# dual_seq_v1_0_1_main.net
KiCad netlist of a schematic drawn in EAGLE
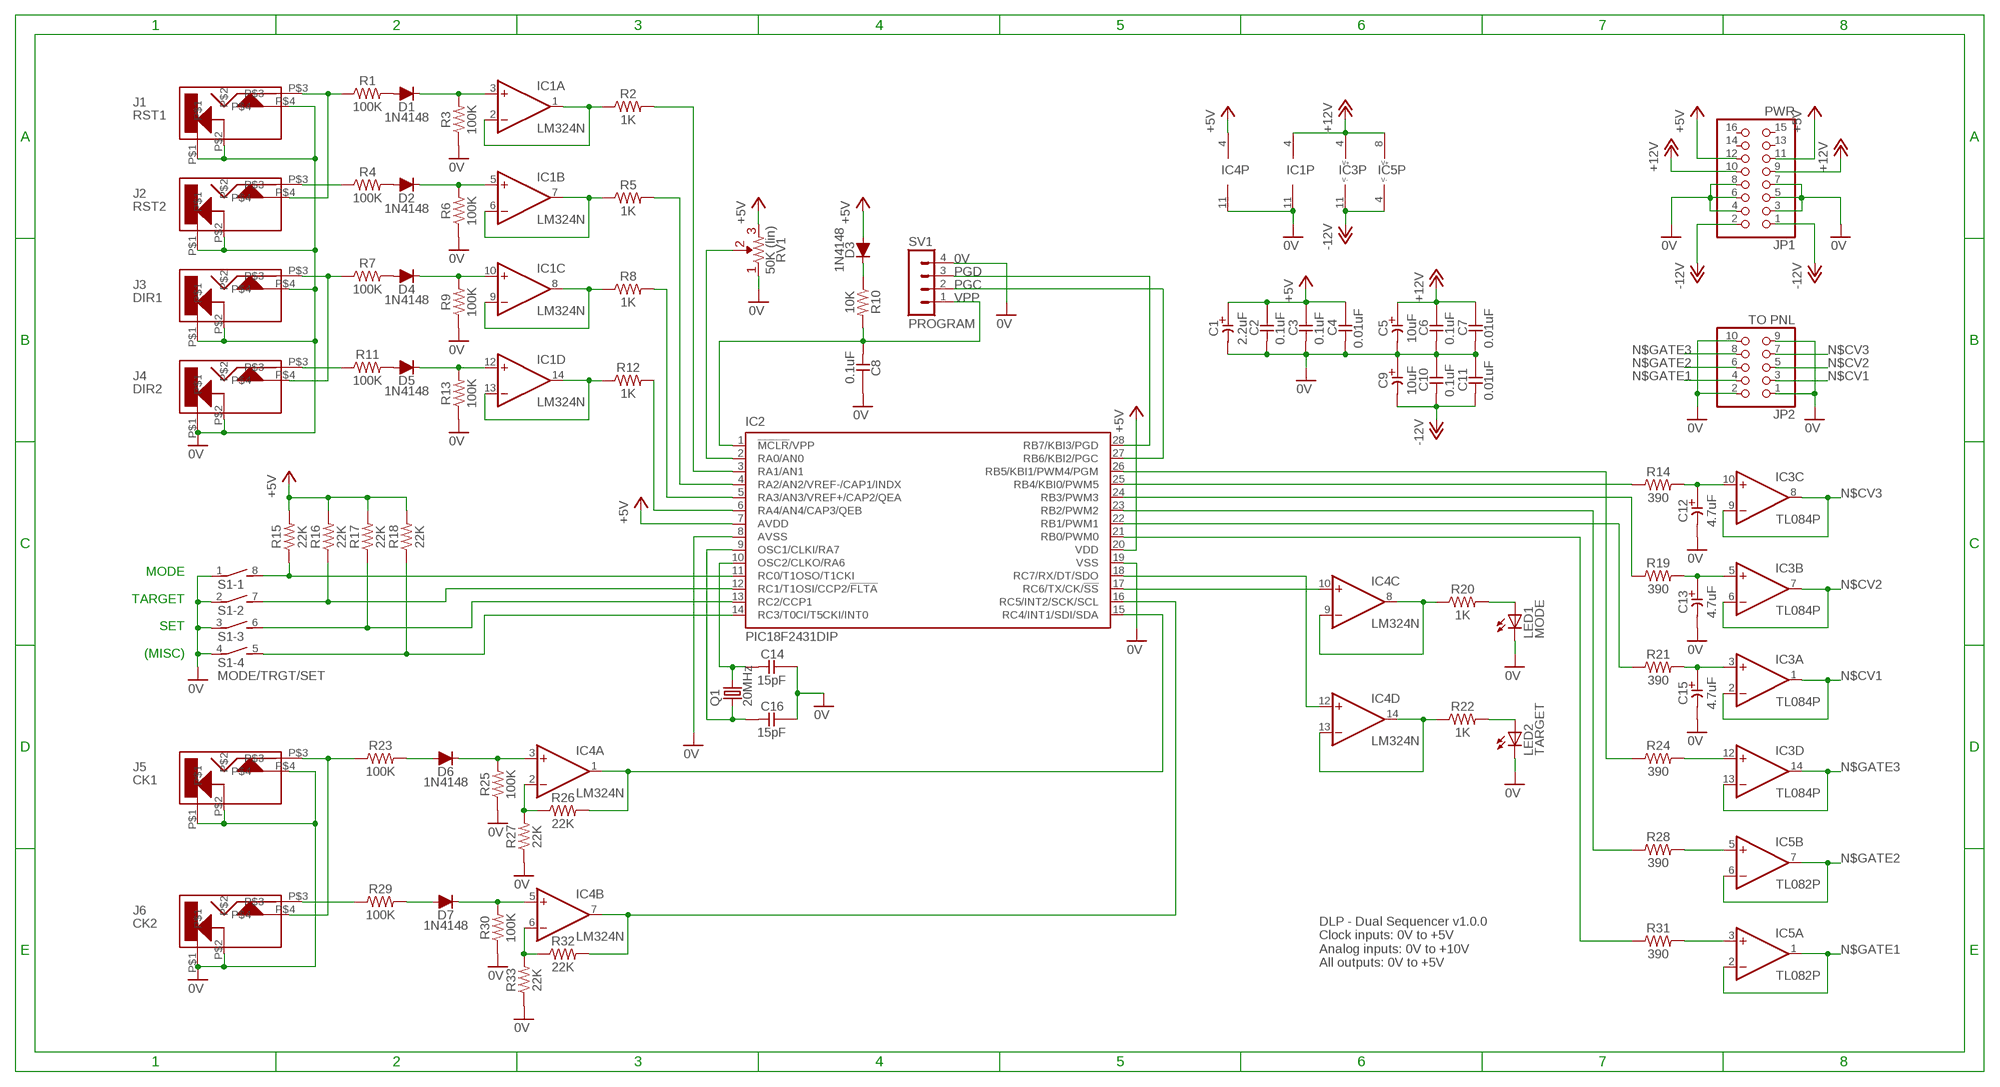
[diagram p0: schematic, sheet 1]

(export (version "E")
  (design (tool "Eeschema 10.0.6"))
  (components
    (comp (ref "C1")
      (value "2.2uF")
      (footprint "eagle-import:E2-5")
      (libsource (lib "eagle-import") (part "CE-USE2-5"))
    )
    (comp (ref "C2")
      (value "0.1uF")
      (footprint "eagle-import:C025-024X044")
      (libsource (lib "eagle-import") (part "CC-US025-024X044"))
    )
    (comp (ref "C3")
      (value "0.1uF")
      (footprint "eagle-import:C025-024X044")
      (libsource (lib "eagle-import") (part "CC-US025-024X044"))
    )
    (comp (ref "C4")
      (value "0.01uF")
      (footprint "eagle-import:C025-024X044")
      (libsource (lib "eagle-import") (part "CC-US025-024X044"))
    )
    (comp (ref "C5")
      (value "10uF")
      (footprint "eagle-import:E2-5")
      (libsource (lib "eagle-import") (part "CE-USE2-5"))
    )
    (comp (ref "C6")
      (value "0.1uF")
      (footprint "eagle-import:C025-024X044")
      (libsource (lib "eagle-import") (part "CC-US025-024X044"))
    )
    (comp (ref "C7")
      (value "0.01uF")
      (footprint "eagle-import:C025-024X044")
      (libsource (lib "eagle-import") (part "CC-US025-024X044"))
    )
    (comp (ref "C8")
      (value "0.1uF")
      (footprint "eagle-import:C025-024X044")
      (libsource (lib "eagle-import") (part "CC-US025-024X044"))
    )
    (comp (ref "C9")
      (value "10uF")
      (footprint "eagle-import:E2-5")
      (libsource (lib "eagle-import") (part "CE-USE2-5"))
    )
    (comp (ref "C10")
      (value "0.1uF")
      (footprint "eagle-import:C025-024X044")
      (libsource (lib "eagle-import") (part "CC-US025-024X044"))
    )
    (comp (ref "C11")
      (value "0.01uF")
      (footprint "eagle-import:C025-024X044")
      (libsource (lib "eagle-import") (part "CC-US025-024X044"))
    )
    (comp (ref "C12")
      (value "4.7uF")
      (footprint "eagle-import:E2-5")
      (libsource (lib "eagle-import") (part "CE-USE2-5"))
    )
    (comp (ref "C13")
      (value "4.7uF")
      (footprint "eagle-import:E2-5")
      (libsource (lib "eagle-import") (part "CE-USE2-5"))
    )
    (comp (ref "C14")
      (value "15pF")
      (footprint "eagle-import:C025-024X044")
      (libsource (lib "eagle-import") (part "CC-US025-024X044"))
    )
    (comp (ref "C15")
      (value "4.7uF")
      (footprint "eagle-import:E2-5")
      (libsource (lib "eagle-import") (part "CE-USE2-5"))
    )
    (comp (ref "C16")
      (value "15pF")
      (footprint "eagle-import:C025-024X044")
      (libsource (lib "eagle-import") (part "CC-US025-024X044"))
    )
    (comp (ref "D1")
      (value "1N4148")
      (footprint "eagle-import:DO34-5")
      (libsource (lib "eagle-import") (part "1N4148"))
    )
    (comp (ref "D2")
      (value "1N4148")
      (footprint "eagle-import:DO34-5")
      (libsource (lib "eagle-import") (part "1N4148"))
    )
    (comp (ref "D3")
      (value "1N4148")
      (footprint "eagle-import:DO34-5")
      (libsource (lib "eagle-import") (part "1N4148"))
    )
    (comp (ref "D4")
      (value "1N4148")
      (footprint "eagle-import:DO34-5")
      (libsource (lib "eagle-import") (part "1N4148"))
    )
    (comp (ref "D5")
      (value "1N4148")
      (footprint "eagle-import:DO34-5")
      (libsource (lib "eagle-import") (part "1N4148"))
    )
    (comp (ref "D6")
      (value "1N4148")
      (footprint "eagle-import:DO34-5")
      (libsource (lib "eagle-import") (part "1N4148"))
    )
    (comp (ref "D7")
      (value "1N4148")
      (footprint "eagle-import:DO34-5")
      (libsource (lib "eagle-import") (part "1N4148"))
    )
    (comp (ref "IC1")
      (value "LM324N")
      (footprint "eagle-import:DIL14")
      (libsource (lib "eagle-import") (part "LM324N"))
    )
    (comp (ref "IC2")
      (value "PIC18F2431DIP")
      (footprint "eagle-import:DIL28-3")
      (fields (field (name "MF") "MICROCHIP") (field (name "MPN") "PIC18F2431-I/SP"))
      (libsource (lib "eagle-import") (part "PIC18F231DIP4"))
    )
    (comp (ref "IC3")
      (value "TL084P")
      (footprint "eagle-import:DIL14")
      (libsource (lib "eagle-import") (part "TL084P"))
    )
    (comp (ref "IC4")
      (value "LM324N")
      (footprint "eagle-import:DIL14")
      (libsource (lib "eagle-import") (part "LM324N"))
    )
    (comp (ref "IC5")
      (value "TL082P")
      (footprint "eagle-import:DIL08")
      (libsource (lib "eagle-import") (part "TL082P"))
    )
    (comp (ref "J1")
      (value "RST1")
      (footprint "eagle-import:CL1384")
      (libsource (lib "eagle-import") (part "CL1384"))
    )
    (comp (ref "J2")
      (value "RST2")
      (footprint "eagle-import:CL1384")
      (libsource (lib "eagle-import") (part "CL1384"))
    )
    (comp (ref "J3")
      (value "DIR1")
      (footprint "eagle-import:CL1384")
      (libsource (lib "eagle-import") (part "CL1384"))
    )
    (comp (ref "J4")
      (value "DIR2")
      (footprint "eagle-import:CL1384")
      (libsource (lib "eagle-import") (part "CL1384"))
    )
    (comp (ref "J5")
      (value "CK1")
      (footprint "eagle-import:CL1384")
      (libsource (lib "eagle-import") (part "CL1384"))
    )
    (comp (ref "J6")
      (value "CK2")
      (footprint "eagle-import:CL1384")
      (libsource (lib "eagle-import") (part "CL1384"))
    )
    (comp (ref "JP1")
      (value "PWR")
      (footprint "eagle-import:2X08")
      (libsource (lib "eagle-import") (part "PINHD-2X8"))
    )
    (comp (ref "JP2")
      (value "TO PNL")
      (footprint "eagle-import:2X05")
      (libsource (lib "eagle-import") (part "PINHD-2X5"))
    )
    (comp (ref "LED1")
      (value "MODE")
      (footprint "eagle-import:LED3MM")
      (libsource (lib "eagle-import") (part "LED3MM"))
    )
    (comp (ref "LED2")
      (value "TARGET")
      (footprint "eagle-import:LED3MM")
      (libsource (lib "eagle-import") (part "LED3MM"))
    )
    (comp (ref "Q1")
      (value "20MHz")
      (footprint "eagle-import:HC49_S")
      (libsource (lib "eagle-import") (part "CRYSTALHC49S"))
    )
    (comp (ref "R1")
      (value "100K")
      (footprint "eagle-import:0207_7")
      (libsource (lib "eagle-import") (part "R"))
    )
    (comp (ref "R2")
      (value "1K")
      (footprint "eagle-import:0207_7")
      (libsource (lib "eagle-import") (part "R"))
    )
    (comp (ref "R3")
      (value "100K")
      (footprint "eagle-import:0207_7")
      (libsource (lib "eagle-import") (part "R"))
    )
    (comp (ref "R4")
      (value "100K")
      (footprint "eagle-import:0207_7")
      (libsource (lib "eagle-import") (part "R"))
    )
    (comp (ref "R5")
      (value "1K")
      (footprint "eagle-import:0207_7")
      (libsource (lib "eagle-import") (part "R"))
    )
    (comp (ref "R6")
      (value "100K")
      (footprint "eagle-import:0207_7")
      (libsource (lib "eagle-import") (part "R"))
    )
    (comp (ref "R7")
      (value "100K")
      (footprint "eagle-import:0207_7")
      (libsource (lib "eagle-import") (part "R"))
    )
    (comp (ref "R8")
      (value "1K")
      (footprint "eagle-import:0207_7")
      (libsource (lib "eagle-import") (part "R"))
    )
    (comp (ref "R9")
      (value "100K")
      (footprint "eagle-import:0207_7")
      (libsource (lib "eagle-import") (part "R"))
    )
    (comp (ref "R10")
      (value "10K")
      (footprint "eagle-import:0207_7")
      (libsource (lib "eagle-import") (part "R"))
    )
    (comp (ref "R11")
      (value "100K")
      (footprint "eagle-import:0207_7")
      (libsource (lib "eagle-import") (part "R"))
    )
    (comp (ref "R12")
      (value "1K")
      (footprint "eagle-import:0207_7")
      (libsource (lib "eagle-import") (part "R"))
    )
    (comp (ref "R13")
      (value "100K")
      (footprint "eagle-import:0207_7")
      (libsource (lib "eagle-import") (part "R"))
    )
    (comp (ref "R14")
      (value "390")
      (footprint "eagle-import:0207_7")
      (libsource (lib "eagle-import") (part "R"))
    )
    (comp (ref "R15")
      (value "22K")
      (footprint "eagle-import:0207_7")
      (libsource (lib "eagle-import") (part "R"))
    )
    (comp (ref "R16")
      (value "22K")
      (footprint "eagle-import:0207_7")
      (libsource (lib "eagle-import") (part "R"))
    )
    (comp (ref "R17")
      (value "22K")
      (footprint "eagle-import:0207_7")
      (libsource (lib "eagle-import") (part "R"))
    )
    (comp (ref "R18")
      (value "22K")
      (footprint "eagle-import:0207_7")
      (libsource (lib "eagle-import") (part "R"))
    )
    (comp (ref "R19")
      (value "390")
      (footprint "eagle-import:0207_7")
      (libsource (lib "eagle-import") (part "R"))
    )
    (comp (ref "R20")
      (value "1K")
      (footprint "eagle-import:0207_7")
      (libsource (lib "eagle-import") (part "R"))
    )
    (comp (ref "R21")
      (value "390")
      (footprint "eagle-import:0207_7")
      (libsource (lib "eagle-import") (part "R"))
    )
    (comp (ref "R22")
      (value "1K")
      (footprint "eagle-import:0207_7")
      (libsource (lib "eagle-import") (part "R"))
    )
    (comp (ref "R23")
      (value "100K")
      (footprint "eagle-import:0207_7")
      (libsource (lib "eagle-import") (part "R"))
    )
    (comp (ref "R24")
      (value "390")
      (footprint "eagle-import:0207_7")
      (libsource (lib "eagle-import") (part "R"))
    )
    (comp (ref "R25")
      (value "100K")
      (footprint "eagle-import:0207_7")
      (libsource (lib "eagle-import") (part "R"))
    )
    (comp (ref "R26")
      (value "22K")
      (footprint "eagle-import:0207_7")
      (libsource (lib "eagle-import") (part "R"))
    )
    (comp (ref "R27")
      (value "22K")
      (footprint "eagle-import:0207_7")
      (libsource (lib "eagle-import") (part "R"))
    )
    (comp (ref "R28")
      (value "390")
      (footprint "eagle-import:0207_7")
      (libsource (lib "eagle-import") (part "R"))
    )
    (comp (ref "R29")
      (value "100K")
      (footprint "eagle-import:0207_7")
      (libsource (lib "eagle-import") (part "R"))
    )
    (comp (ref "R30")
      (value "100K")
      (footprint "eagle-import:0207_7")
      (libsource (lib "eagle-import") (part "R"))
    )
    (comp (ref "R31")
      (value "390")
      (footprint "eagle-import:0207_7")
      (libsource (lib "eagle-import") (part "R"))
    )
    (comp (ref "R32")
      (value "22K")
      (footprint "eagle-import:0207_7")
      (libsource (lib "eagle-import") (part "R"))
    )
    (comp (ref "R33")
      (value "22K")
      (footprint "eagle-import:0207_7")
      (libsource (lib "eagle-import") (part "R"))
    )
    (comp (ref "RV1")
      (value "50K (lin)")
      (footprint "eagle-import:R-VAR")
      (libsource (lib "eagle-import") (part "R-VAR"))
    )
    (comp (ref "S1")
      (value "MODE/TRGT/SET")
      (footprint "eagle-import:DIP04S")
      (libsource (lib "eagle-import") (part "DIP04S"))
    )
    (comp (ref "SV1")
      (value "PROGRAM")
      (footprint "eagle-import:MA04-1")
      (libsource (lib "eagle-import") (part "MA04-1"))
    )
  )
  (nets
    (net (code "1") (name "+5V") (class "Default")
      (node (ref "C1") (pin "+") (pinfunction "+_+") (pintype "passive"))
      (node (ref "C2") (pin "1") (pinfunction "1_1") (pintype "passive"))
      (node (ref "C3") (pin "1") (pinfunction "1_1") (pintype "passive"))
      (node (ref "C4") (pin "1") (pinfunction "1_1") (pintype "passive"))
      (node (ref "D3") (pin "A") (pinfunction "A_A") (pintype "passive"))
      (node (ref "IC2") (pin "20") (pinfunction "VDD_20") (pintype "power_in"))
      (node (ref "IC2") (pin "7") (pinfunction "AVDD_7") (pintype "power_in"))
      (node (ref "IC4") (pin "4") (pinfunction "V+_4") (pintype "power_in"))
      (node (ref "JP1") (pin "11") (pinfunction "11_11") (pintype "passive"))
      (node (ref "JP1") (pin "12") (pinfunction "12_12") (pintype "passive"))
      (node (ref "R15") (pin "2") (pinfunction "2_2") (pintype "passive"))
      (node (ref "R16") (pin "2") (pinfunction "2_2") (pintype "passive"))
      (node (ref "R17") (pin "2") (pinfunction "2_2") (pintype "passive"))
      (node (ref "R18") (pin "2") (pinfunction "2_2") (pintype "passive"))
      (node (ref "RV1") (pin "R2") (pinfunction "2_R2") (pintype "passive"))
    )
    (net (code "2") (name "+12V") (class "Default")
      (node (ref "C5") (pin "+") (pinfunction "+_+") (pintype "passive"))
      (node (ref "C6") (pin "1") (pinfunction "1_1") (pintype "passive"))
      (node (ref "C7") (pin "1") (pinfunction "1_1") (pintype "passive"))
      (node (ref "IC1") (pin "4") (pinfunction "V+_4") (pintype "power_in"))
      (node (ref "IC3") (pin "4") (pinfunction "V+_4") (pintype "power_in"))
      (node (ref "IC5") (pin "8") (pinfunction "V+_8") (pintype "power_in"))
      (node (ref "JP1") (pin "10") (pinfunction "10_10") (pintype "passive"))
      (node (ref "JP1") (pin "9") (pinfunction "9_9") (pintype "passive"))
    )
    (net (code "3") (name "-12V") (class "Default")
      (node (ref "C10") (pin "2") (pinfunction "2_2") (pintype "passive"))
      (node (ref "C11") (pin "2") (pinfunction "2_2") (pintype "passive"))
      (node (ref "C9") (pin "-") (pinfunction "-_-") (pintype "passive"))
      (node (ref "IC3") (pin "11") (pinfunction "V-_11") (pintype "power_in"))
      (node (ref "IC5") (pin "4") (pinfunction "V-_4") (pintype "power_in"))
      (node (ref "JP1") (pin "1") (pinfunction "1_1") (pintype "passive"))
      (node (ref "JP1") (pin "2") (pinfunction "2_2") (pintype "passive"))
    )
    (net (code "4") (name "/N$CV1") (class "Default")
      (node (ref "IC3") (pin "1") (pinfunction "OUT_1") (pintype "output"))
      (node (ref "IC3") (pin "2") (pinfunction "-IN_2") (pintype "input"))
      (node (ref "JP2") (pin "3") (pinfunction "3_3") (pintype "passive"))
    )
    (net (code "5") (name "/N$CV2") (class "Default")
      (node (ref "IC3") (pin "6") (pinfunction "-IN_6") (pintype "input"))
      (node (ref "IC3") (pin "7") (pinfunction "OUT_7") (pintype "output"))
      (node (ref "JP2") (pin "5") (pinfunction "5_5") (pintype "passive"))
    )
    (net (code "6") (name "/N$CV3") (class "Default")
      (node (ref "IC3") (pin "8") (pinfunction "OUT_8") (pintype "output"))
      (node (ref "IC3") (pin "9") (pinfunction "-IN_9") (pintype "input"))
      (node (ref "JP2") (pin "7") (pinfunction "7_7") (pintype "passive"))
    )
    (net (code "7") (name "/N$GATE1") (class "Default")
      (node (ref "IC5") (pin "1") (pinfunction "OUT_1") (pintype "output"))
      (node (ref "IC5") (pin "2") (pinfunction "-IN_2") (pintype "input"))
      (node (ref "JP2") (pin "4") (pinfunction "4_4") (pintype "passive"))
    )
    (net (code "8") (name "/N$GATE2") (class "Default")
      (node (ref "IC5") (pin "6") (pinfunction "-IN_6") (pintype "input"))
      (node (ref "IC5") (pin "7") (pinfunction "OUT_7") (pintype "output"))
      (node (ref "JP2") (pin "6") (pinfunction "6_6") (pintype "passive"))
    )
    (net (code "9") (name "/N$GATE3") (class "Default")
      (node (ref "IC3") (pin "13") (pinfunction "-IN_13") (pintype "input"))
      (node (ref "IC3") (pin "14") (pinfunction "OUT_14") (pintype "output"))
      (node (ref "JP2") (pin "8") (pinfunction "8_8") (pintype "passive"))
    )
    (net (code "10") (name "/PGC") (class "Default")
      (node (ref "IC2") (pin "27") (pinfunction "RB6/KBI2/PGC_27") (pintype "bidirectional"))
      (node (ref "SV1") (pin "2") (pinfunction "2_2") (pintype "passive"))
    )
    (net (code "11") (name "/PGD") (class "Default")
      (node (ref "IC2") (pin "28") (pinfunction "RB7/KBI3/PGD_28") (pintype "bidirectional"))
      (node (ref "SV1") (pin "3") (pinfunction "3_3") (pintype "passive"))
    )
    (net (code "12") (name "/VPP") (class "Default")
      (node (ref "C8") (pin "2") (pinfunction "2_2") (pintype "passive"))
      (node (ref "IC2") (pin "1") (pinfunction "~{MCLR}/VPP_1") (pintype "input"))
      (node (ref "R10") (pin "2") (pinfunction "2_2") (pintype "passive"))
      (node (ref "SV1") (pin "1") (pinfunction "1_1") (pintype "passive"))
    )
    (net (code "13") (name "0V") (class "Default")
      (node (ref "C1") (pin "-") (pinfunction "-_-") (pintype "passive"))
      (node (ref "C10") (pin "1") (pinfunction "1_1") (pintype "passive"))
      (node (ref "C11") (pin "1") (pinfunction "1_1") (pintype "passive"))
      (node (ref "C12") (pin "-") (pinfunction "-_-") (pintype "passive"))
      (node (ref "C13") (pin "-") (pinfunction "-_-") (pintype "passive"))
      (node (ref "C14") (pin "1") (pinfunction "1_1") (pintype "passive"))
      (node (ref "C15") (pin "-") (pinfunction "-_-") (pintype "passive"))
      (node (ref "C16") (pin "1") (pinfunction "1_1") (pintype "passive"))
      (node (ref "C2") (pin "2") (pinfunction "2_2") (pintype "passive"))
      (node (ref "C3") (pin "2") (pinfunction "2_2") (pintype "passive"))
      (node (ref "C4") (pin "2") (pinfunction "2_2") (pintype "passive"))
      (node (ref "C5") (pin "-") (pinfunction "-_-") (pintype "passive"))
      (node (ref "C6") (pin "2") (pinfunction "2_2") (pintype "passive"))
      (node (ref "C7") (pin "2") (pinfunction "2_2") (pintype "passive"))
      (node (ref "C8") (pin "1") (pinfunction "1_1") (pintype "passive"))
      (node (ref "C9") (pin "+") (pinfunction "+_+") (pintype "passive"))
      (node (ref "IC1") (pin "11") (pinfunction "V-_11") (pintype "power_in"))
      (node (ref "IC2") (pin "19") (pinfunction "VSS_19") (pintype "power_in"))
      (node (ref "IC2") (pin "8") (pinfunction "AVSS_8") (pintype "power_in"))
      (node (ref "IC4") (pin "11") (pinfunction "V-_11") (pintype "power_in"))
      (node (ref "J1") (pin "P$1") (pinfunction "P$1_P$1") (pintype "bidirectional"))
      (node (ref "J1") (pin "P$2") (pinfunction "P$2_P$2") (pintype "bidirectional"))
      (node (ref "J1") (pin "P$4") (pinfunction "P$4_P$4") (pintype "bidirectional"))
      (node (ref "J2") (pin "P$1") (pinfunction "P$1_P$1") (pintype "bidirectional"))
      (node (ref "J2") (pin "P$2") (pinfunction "P$2_P$2") (pintype "bidirectional"))
      (node (ref "J3") (pin "P$1") (pinfunction "P$1_P$1") (pintype "bidirectional"))
      (node (ref "J3") (pin "P$2") (pinfunction "P$2_P$2") (pintype "bidirectional"))
      (node (ref "J3") (pin "P$4") (pinfunction "P$4_P$4") (pintype "bidirectional"))
      (node (ref "J4") (pin "P$1") (pinfunction "P$1_P$1") (pintype "bidirectional"))
      (node (ref "J4") (pin "P$2") (pinfunction "P$2_P$2") (pintype "bidirectional"))
      (node (ref "J5") (pin "P$1") (pinfunction "P$1_P$1") (pintype "bidirectional"))
      (node (ref "J5") (pin "P$2") (pinfunction "P$2_P$2") (pintype "bidirectional"))
      (node (ref "J5") (pin "P$4") (pinfunction "P$4_P$4") (pintype "bidirectional"))
      (node (ref "J6") (pin "P$1") (pinfunction "P$1_P$1") (pintype "bidirectional"))
      (node (ref "J6") (pin "P$2") (pinfunction "P$2_P$2") (pintype "bidirectional"))
      (node (ref "JP1") (pin "3") (pinfunction "3_3") (pintype "passive"))
      (node (ref "JP1") (pin "4") (pinfunction "4_4") (pintype "passive"))
      (node (ref "JP1") (pin "5") (pinfunction "5_5") (pintype "passive"))
      (node (ref "JP1") (pin "6") (pinfunction "6_6") (pintype "passive"))
      (node (ref "JP1") (pin "7") (pinfunction "7_7") (pintype "passive"))
      (node (ref "JP1") (pin "8") (pinfunction "8_8") (pintype "passive"))
      (node (ref "JP2") (pin "1") (pinfunction "1_1") (pintype "passive"))
      (node (ref "JP2") (pin "10") (pinfunction "10_10") (pintype "passive"))
      (node (ref "JP2") (pin "2") (pinfunction "2_2") (pintype "passive"))
      (node (ref "JP2") (pin "9") (pinfunction "9_9") (pintype "passive"))
      (node (ref "LED1") (pin "K") (pinfunction "C_K") (pintype "passive"))
      (node (ref "LED2") (pin "K") (pinfunction "C_K") (pintype "passive"))
      (node (ref "R13") (pin "1") (pinfunction "1_1") (pintype "passive"))
      (node (ref "R25") (pin "1") (pinfunction "1_1") (pintype "passive"))
      (node (ref "R27") (pin "1") (pinfunction "1_1") (pintype "passive"))
      (node (ref "R3") (pin "1") (pinfunction "1_1") (pintype "passive"))
      (node (ref "R30") (pin "1") (pinfunction "1_1") (pintype "passive"))
      (node (ref "R33") (pin "1") (pinfunction "1_1") (pintype "passive"))
      (node (ref "R6") (pin "1") (pinfunction "1_1") (pintype "passive"))
      (node (ref "R9") (pin "1") (pinfunction "1_1") (pintype "passive"))
      (node (ref "RV1") (pin "R1") (pinfunction "1_R1") (pintype "passive"))
      (node (ref "S1") (pin "1") (pinfunction "1_1") (pintype "passive"))
      (node (ref "S1") (pin "2") (pinfunction "1_2") (pintype "passive"))
      (node (ref "S1") (pin "3") (pinfunction "1_3") (pintype "passive"))
      (node (ref "S1") (pin "4") (pinfunction "1_4") (pintype "passive"))
      (node (ref "SV1") (pin "4") (pinfunction "4_4") (pintype "passive"))
    )
    (net (code "14") (name "Net-(D1-PadA)") (class "Default")
      (node (ref "D1") (pin "A") (pinfunction "A_A") (pintype "passive"))
      (node (ref "R1") (pin "2") (pinfunction "2_2") (pintype "passive"))
    )
    (net (code "15") (name "Net-(D2-PadA)") (class "Default")
      (node (ref "D2") (pin "A") (pinfunction "A_A") (pintype "passive"))
      (node (ref "R4") (pin "2") (pinfunction "2_2") (pintype "passive"))
    )
    (net (code "16") (name "Net-(D3-PadC)") (class "Default")
      (node (ref "D3") (pin "C") (pinfunction "C_C") (pintype "passive"))
      (node (ref "R10") (pin "1") (pinfunction "1_1") (pintype "passive"))
    )
    (net (code "17") (name "Net-(D4-PadA)") (class "Default")
      (node (ref "D4") (pin "A") (pinfunction "A_A") (pintype "passive"))
      (node (ref "R7") (pin "2") (pinfunction "2_2") (pintype "passive"))
    )
    (net (code "18") (name "Net-(D5-PadA)") (class "Default")
      (node (ref "D5") (pin "A") (pinfunction "A_A") (pintype "passive"))
      (node (ref "R11") (pin "2") (pinfunction "2_2") (pintype "passive"))
    )
    (net (code "19") (name "Net-(D6-PadA)") (class "Default")
      (node (ref "D6") (pin "A") (pinfunction "A_A") (pintype "passive"))
      (node (ref "R23") (pin "2") (pinfunction "2_2") (pintype "passive"))
    )
    (net (code "20") (name "Net-(D7-PadA)") (class "Default")
      (node (ref "D7") (pin "A") (pinfunction "A_A") (pintype "passive"))
      (node (ref "R29") (pin "2") (pinfunction "2_2") (pintype "passive"))
    )
    (net (code "21") (name "Net-(IC1A-+IN)") (class "Default")
      (node (ref "D1") (pin "C") (pinfunction "C_C") (pintype "passive"))
      (node (ref "IC1") (pin "3") (pinfunction "+IN_3") (pintype "input"))
      (node (ref "R3") (pin "2") (pinfunction "2_2") (pintype "passive"))
    )
    (net (code "22") (name "Net-(IC1A--IN)") (class "Default")
      (node (ref "IC1") (pin "1") (pinfunction "OUT_1") (pintype "output"))
      (node (ref "IC1") (pin "2") (pinfunction "-IN_2") (pintype "input"))
      (node (ref "R2") (pin "1") (pinfunction "1_1") (pintype "passive"))
    )
    (net (code "23") (name "Net-(IC1B-+IN)") (class "Default")
      (node (ref "D2") (pin "C") (pinfunction "C_C") (pintype "passive"))
      (node (ref "IC1") (pin "5") (pinfunction "+IN_5") (pintype "input"))
      (node (ref "R6") (pin "2") (pinfunction "2_2") (pintype "passive"))
    )
    (net (code "24") (name "Net-(IC1B--IN)") (class "Default")
      (node (ref "IC1") (pin "6") (pinfunction "-IN_6") (pintype "input"))
      (node (ref "IC1") (pin "7") (pinfunction "OUT_7") (pintype "output"))
      (node (ref "R5") (pin "1") (pinfunction "1_1") (pintype "passive"))
    )
    (net (code "25") (name "Net-(IC1C-+IN)") (class "Default")
      (node (ref "D4") (pin "C") (pinfunction "C_C") (pintype "passive"))
      (node (ref "IC1") (pin "10") (pinfunction "+IN_10") (pintype "input"))
      (node (ref "R9") (pin "2") (pinfunction "2_2") (pintype "passive"))
    )
    (net (code "26") (name "Net-(IC1C--IN)") (class "Default")
      (node (ref "IC1") (pin "8") (pinfunction "OUT_8") (pintype "output"))
      (node (ref "IC1") (pin "9") (pinfunction "-IN_9") (pintype "input"))
      (node (ref "R8") (pin "1") (pinfunction "1_1") (pintype "passive"))
    )
    (net (code "27") (name "Net-(IC1D-+IN)") (class "Default")
      (node (ref "D5") (pin "C") (pinfunction "C_C") (pintype "passive"))
      (node (ref "IC1") (pin "12") (pinfunction "+IN_12") (pintype "input"))
      (node (ref "R13") (pin "2") (pinfunction "2_2") (pintype "passive"))
    )
    (net (code "28") (name "Net-(IC1D--IN)") (class "Default")
      (node (ref "IC1") (pin "13") (pinfunction "-IN_13") (pintype "input"))
      (node (ref "IC1") (pin "14") (pinfunction "OUT_14") (pintype "output"))
      (node (ref "R12") (pin "1") (pinfunction "1_1") (pintype "passive"))
    )
    (net (code "29") (name "Net-(IC2-OSC1{slash}CLKI{slash}RA7)") (class "Default")
      (node (ref "C16") (pin "2") (pinfunction "2_2") (pintype "passive"))
      (node (ref "IC2") (pin "9") (pinfunction "OSC1/CLKI/RA7_9") (pintype "input"))
      (node (ref "Q1") (pin "1") (pinfunction "1_1") (pintype "passive"))
    )
    (net (code "30") (name "Net-(IC2-OSC2{slash}CLKO{slash}RA6)") (class "Default")
      (node (ref "C14") (pin "2") (pinfunction "2_2") (pintype "passive"))
      (node (ref "IC2") (pin "10") (pinfunction "OSC2/CLKO/RA6_10") (pintype "output"))
      (node (ref "Q1") (pin "2") (pinfunction "2_2") (pintype "passive"))
    )
    (net (code "31") (name "Net-(IC2-RA0{slash}AN0)") (class "Default")
      (node (ref "IC2") (pin "2") (pinfunction "RA0/AN0_2") (pintype "bidirectional"))
      (node (ref "RV1") (pin "VAR") (pinfunction "P$1_VAR") (pintype "passive"))
    )
    (net (code "32") (name "Net-(IC2-RA1{slash}AN1)") (class "Default")
      (node (ref "IC2") (pin "3") (pinfunction "RA1/AN1_3") (pintype "bidirectional"))
      (node (ref "R2") (pin "2") (pinfunction "2_2") (pintype "passive"))
    )
    (net (code "33") (name "Net-(IC2-RA2{slash}AN2{slash}VREF-{slash}CAP1{slash}INDX)") (class "Default")
      (node (ref "IC2") (pin "4") (pinfunction "RA2/AN2/VREF-/CAP1/INDX_4") (pintype "bidirectional"))
      (node (ref "R5") (pin "2") (pinfunction "2_2") (pintype "passive"))
    )
    (net (code "34") (name "Net-(IC2-RA3{slash}AN3{slash}VREF+{slash}CAP2{slash}QEA)") (class "Default")
      (node (ref "IC2") (pin "5") (pinfunction "RA3/AN3/VREF+/CAP2/QEA_5") (pintype "bidirectional"))
      (node (ref "R8") (pin "2") (pinfunction "2_2") (pintype "passive"))
    )
    (net (code "35") (name "Net-(IC2-RA4{slash}AN4{slash}CAP3{slash}QEB)") (class "Default")
      (node (ref "IC2") (pin "6") (pinfunction "RA4/AN4/CAP3/QEB_6") (pintype "bidirectional"))
      (node (ref "R12") (pin "2") (pinfunction "2_2") (pintype "passive"))
    )
    (net (code "36") (name "Net-(IC2-RB0{slash}PWM0)") (class "Default")
      (node (ref "IC2") (pin "21") (pinfunction "RB0/PWM0_21") (pintype "bidirectional"))
      (node (ref "R31") (pin "1") (pinfunction "1_1") (pintype "passive"))
    )
    (net (code "37") (name "Net-(IC2-RB1{slash}PWM1)") (class "Default")
      (node (ref "IC2") (pin "22") (pinfunction "RB1/PWM1_22") (pintype "bidirectional"))
      (node (ref "R21") (pin "1") (pinfunction "1_1") (pintype "passive"))
    )
    (net (code "38") (name "Net-(IC2-RB2{slash}PWM2)") (class "Default")
      (node (ref "IC2") (pin "23") (pinfunction "RB2/PWM2_23") (pintype "bidirectional"))
      (node (ref "R28") (pin "1") (pinfunction "1_1") (pintype "passive"))
    )
    (net (code "39") (name "Net-(IC2-RB3{slash}PWM3)") (class "Default")
      (node (ref "IC2") (pin "24") (pinfunction "RB3/PWM3_24") (pintype "bidirectional"))
      (node (ref "R19") (pin "1") (pinfunction "1_1") (pintype "passive"))
    )
    (net (code "40") (name "Net-(IC2-RB4{slash}KBI0{slash}PWM5)") (class "Default")
      (node (ref "IC2") (pin "25") (pinfunction "RB4/KBI0/PWM5_25") (pintype "bidirectional"))
      (node (ref "R14") (pin "1") (pinfunction "1_1") (pintype "passive"))
    )
    (net (code "41") (name "Net-(IC2-RB5{slash}KBI1{slash}PWM4{slash}PGM)") (class "Default")
      (node (ref "IC2") (pin "26") (pinfunction "RB5/KBI1/PWM4/PGM_26") (pintype "bidirectional"))
      (node (ref "R24") (pin "1") (pinfunction "1_1") (pintype "passive"))
    )
    (net (code "42") (name "Net-(IC2-RC0{slash}T1OSO{slash}T1CKI)") (class "Default")
      (node (ref "IC2") (pin "11") (pinfunction "RC0/T1OSO/T1CKI_11") (pintype "bidirectional"))
      (node (ref "R15") (pin "1") (pinfunction "1_1") (pintype "passive"))
      (node (ref "S1") (pin "8") (pinfunction "2_8") (pintype "passive"))
    )
    (net (code "43") (name "Net-(IC2-RC1{slash}T1OSI{slash}CCP2{slash}~{FLTA})") (class "Default")
      (node (ref "IC2") (pin "12") (pinfunction "RC1/T1OSI/CCP2/~{FLTA}_12") (pintype "bidirectional"))
      (node (ref "R16") (pin "1") (pinfunction "1_1") (pintype "passive"))
      (node (ref "S1") (pin "7") (pinfunction "2_7") (pintype "passive"))
    )
    (net (code "44") (name "Net-(IC2-RC2{slash}CCP1)") (class "Default")
      (node (ref "IC2") (pin "13") (pinfunction "RC2/CCP1_13") (pintype "bidirectional"))
      (node (ref "R17") (pin "1") (pinfunction "1_1") (pintype "passive"))
      (node (ref "S1") (pin "6") (pinfunction "2_6") (pintype "passive"))
    )
    (net (code "45") (name "Net-(IC2-RC3{slash}T0CI{slash}T5CKI{slash}INT0)") (class "Default")
      (node (ref "IC2") (pin "14") (pinfunction "RC3/T0CI/T5CKI/INT0_14") (pintype "bidirectional"))
      (node (ref "R18") (pin "1") (pinfunction "1_1") (pintype "passive"))
      (node (ref "S1") (pin "5") (pinfunction "2_5") (pintype "passive"))
    )
    (net (code "46") (name "Net-(IC2-RC4{slash}INT1{slash}SDI{slash}SDA)") (class "Default")
      (node (ref "IC2") (pin "15") (pinfunction "RC4/INT1/SDI/SDA_15") (pintype "bidirectional"))
      (node (ref "IC4") (pin "1") (pinfunction "OUT_1") (pintype "output"))
      (node (ref "R26") (pin "2") (pinfunction "2_2") (pintype "passive"))
    )
    (net (code "47") (name "Net-(IC2-RC5{slash}INT2{slash}SCK{slash}SCL)") (class "Default")
      (node (ref "IC2") (pin "16") (pinfunction "RC5/INT2/SCK/SCL_16") (pintype "bidirectional"))
      (node (ref "IC4") (pin "7") (pinfunction "OUT_7") (pintype "output"))
      (node (ref "R32") (pin "2") (pinfunction "2_2") (pintype "passive"))
    )
    (net (code "48") (name "Net-(IC2-RC6{slash}TX{slash}CK{slash}~{SS})") (class "Default")
      (node (ref "IC2") (pin "17") (pinfunction "RC6/TX/CK/~{SS}_17") (pintype "bidirectional"))
      (node (ref "IC4") (pin "10") (pinfunction "+IN_10") (pintype "input"))
    )
    (net (code "49") (name "Net-(IC2-RC7{slash}RX{slash}DT{slash}SDO)") (class "Default")
      (node (ref "IC2") (pin "18") (pinfunction "RC7/RX/DT/SDO_18") (pintype "bidirectional"))
      (node (ref "IC4") (pin "12") (pinfunction "+IN_12") (pintype "input"))
    )
    (net (code "50") (name "Net-(IC3A-+IN)") (class "Default")
      (node (ref "C15") (pin "+") (pinfunction "+_+") (pintype "passive"))
      (node (ref "IC3") (pin "3") (pinfunction "+IN_3") (pintype "input"))
      (node (ref "R21") (pin "2") (pinfunction "2_2") (pintype "passive"))
    )
    (net (code "51") (name "Net-(IC3B-+IN)") (class "Default")
      (node (ref "C13") (pin "+") (pinfunction "+_+") (pintype "passive"))
      (node (ref "IC3") (pin "5") (pinfunction "+IN_5") (pintype "input"))
      (node (ref "R19") (pin "2") (pinfunction "2_2") (pintype "passive"))
    )
    (net (code "52") (name "Net-(IC3C-+IN)") (class "Default")
      (node (ref "C12") (pin "+") (pinfunction "+_+") (pintype "passive"))
      (node (ref "IC3") (pin "10") (pinfunction "+IN_10") (pintype "input"))
      (node (ref "R14") (pin "2") (pinfunction "2_2") (pintype "passive"))
    )
    (net (code "53") (name "Net-(IC3D-+IN)") (class "Default")
      (node (ref "IC3") (pin "12") (pinfunction "+IN_12") (pintype "input"))
      (node (ref "R24") (pin "2") (pinfunction "2_2") (pintype "passive"))
    )
    (net (code "54") (name "Net-(IC4A-+IN)") (class "Default")
      (node (ref "D6") (pin "C") (pinfunction "C_C") (pintype "passive"))
      (node (ref "IC4") (pin "3") (pinfunction "+IN_3") (pintype "input"))
      (node (ref "R25") (pin "2") (pinfunction "2_2") (pintype "passive"))
    )
    (net (code "55") (name "Net-(IC4A--IN)") (class "Default")
      (node (ref "IC4") (pin "2") (pinfunction "-IN_2") (pintype "input"))
      (node (ref "R26") (pin "1") (pinfunction "1_1") (pintype "passive"))
      (node (ref "R27") (pin "2") (pinfunction "2_2") (pintype "passive"))
    )
    (net (code "56") (name "Net-(IC4B-+IN)") (class "Default")
      (node (ref "D7") (pin "C") (pinfunction "C_C") (pintype "passive"))
      (node (ref "IC4") (pin "5") (pinfunction "+IN_5") (pintype "input"))
      (node (ref "R30") (pin "2") (pinfunction "2_2") (pintype "passive"))
    )
    (net (code "57") (name "Net-(IC4B--IN)") (class "Default")
      (node (ref "IC4") (pin "6") (pinfunction "-IN_6") (pintype "input"))
      (node (ref "R32") (pin "1") (pinfunction "1_1") (pintype "passive"))
      (node (ref "R33") (pin "2") (pinfunction "2_2") (pintype "passive"))
    )
    (net (code "58") (name "Net-(IC4C--IN)") (class "Default")
      (node (ref "IC4") (pin "8") (pinfunction "OUT_8") (pintype "output"))
      (node (ref "IC4") (pin "9") (pinfunction "-IN_9") (pintype "input"))
      (node (ref "R20") (pin "1") (pinfunction "1_1") (pintype "passive"))
    )
    (net (code "59") (name "Net-(IC4D--IN)") (class "Default")
      (node (ref "IC4") (pin "13") (pinfunction "-IN_13") (pintype "input"))
      (node (ref "IC4") (pin "14") (pinfunction "OUT_14") (pintype "output"))
      (node (ref "R22") (pin "1") (pinfunction "1_1") (pintype "passive"))
    )
    (net (code "60") (name "Net-(IC5A-+IN)") (class "Default")
      (node (ref "IC5") (pin "3") (pinfunction "+IN_3") (pintype "input"))
      (node (ref "R31") (pin "2") (pinfunction "2_2") (pintype "passive"))
    )
    (net (code "61") (name "Net-(IC5B-+IN)") (class "Default")
      (node (ref "IC5") (pin "5") (pinfunction "+IN_5") (pintype "input"))
      (node (ref "R28") (pin "2") (pinfunction "2_2") (pintype "passive"))
    )
    (net (code "62") (name "Net-(J1-PadP$3)") (class "Default")
      (node (ref "J1") (pin "P$3") (pinfunction "P$3_P$3") (pintype "bidirectional"))
      (node (ref "J2") (pin "P$4") (pinfunction "P$4_P$4") (pintype "bidirectional"))
      (node (ref "R1") (pin "1") (pinfunction "1_1") (pintype "passive"))
    )
    (net (code "63") (name "Net-(J2-PadP$3)") (class "Default")
      (node (ref "J2") (pin "P$3") (pinfunction "P$3_P$3") (pintype "bidirectional"))
      (node (ref "R4") (pin "1") (pinfunction "1_1") (pintype "passive"))
    )
    (net (code "64") (name "Net-(J3-PadP$3)") (class "Default")
      (node (ref "J3") (pin "P$3") (pinfunction "P$3_P$3") (pintype "bidirectional"))
      (node (ref "J4") (pin "P$4") (pinfunction "P$4_P$4") (pintype "bidirectional"))
      (node (ref "R7") (pin "1") (pinfunction "1_1") (pintype "passive"))
    )
    (net (code "65") (name "Net-(J4-PadP$3)") (class "Default")
      (node (ref "J4") (pin "P$3") (pinfunction "P$3_P$3") (pintype "bidirectional"))
      (node (ref "R11") (pin "1") (pinfunction "1_1") (pintype "passive"))
    )
    (net (code "66") (name "Net-(J5-PadP$3)") (class "Default")
      (node (ref "J5") (pin "P$3") (pinfunction "P$3_P$3") (pintype "bidirectional"))
      (node (ref "J6") (pin "P$4") (pinfunction "P$4_P$4") (pintype "bidirectional"))
      (node (ref "R23") (pin "1") (pinfunction "1_1") (pintype "passive"))
    )
    (net (code "67") (name "Net-(J6-PadP$3)") (class "Default")
      (node (ref "J6") (pin "P$3") (pinfunction "P$3_P$3") (pintype "bidirectional"))
      (node (ref "R29") (pin "1") (pinfunction "1_1") (pintype "passive"))
    )
    (net (code "68") (name "Net-(LED1-PadA)") (class "Default")
      (node (ref "LED1") (pin "A") (pinfunction "A_A") (pintype "passive"))
      (node (ref "R20") (pin "2") (pinfunction "2_2") (pintype "passive"))
    )
    (net (code "69") (name "Net-(LED2-PadA)") (class "Default")
      (node (ref "LED2") (pin "A") (pinfunction "A_A") (pintype "passive"))
      (node (ref "R22") (pin "2") (pinfunction "2_2") (pintype "passive"))
    )
    (net (code "70") (name "unconnected-(JP1-Pad13)") (class "Default")
      (node (ref "JP1") (pin "13") (pinfunction "13_13") (pintype "passive"))
    )
    (net (code "71") (name "unconnected-(JP1-Pad14)") (class "Default")
      (node (ref "JP1") (pin "14") (pinfunction "14_14") (pintype "passive"))
    )
    (net (code "72") (name "unconnected-(JP1-Pad15)") (class "Default")
      (node (ref "JP1") (pin "15") (pinfunction "15_15") (pintype "passive"))
    )
    (net (code "73") (name "unconnected-(JP1-Pad16)") (class "Default")
      (node (ref "JP1") (pin "16") (pinfunction "16_16") (pintype "passive"))
    )
  )
)
